# 5.net
KiCad netlist of a schematic drawn in EAGLE
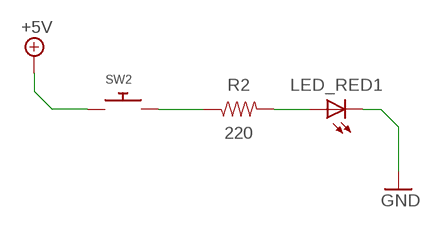
[diagram p0: schematic, sheet 1]
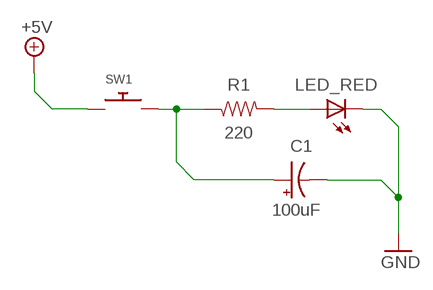
[diagram p1: schematic, sheet 2]

(export (version "E")
  (design (tool "Eeschema 10.0.6"))
  (components
    (comp (ref "LED_RED1")
      (value "LED5MM")
      (footprint "eagle-import:LED5MM")
      (libsource (lib "eagle-import") (part "LED5MM"))
    )
    (comp (ref "R2")
      (value "220")
      (footprint "eagle-import:AXIAL-0.3")
      (libsource (lib "eagle-import") (part "100OHM-HORIZ-1/4W-1%"))
    )
    (comp (ref "SW2")
      (value "SWITCH_PUSHBUTTONSOFTTOUCHSMD_SJ")
      (footprint "eagle-import:PUSHBUTTON_SMD_SJ")
      (libsource (lib "eagle-import") (part "SWITCH_PUSHBUTTONSOFTTOUCHSMD_SJ"))
    )
    (comp (ref "C1")
      (value "100uF")
      (footprint "eagle-import:CPOL-RADIAL-2.5MM-6.5MM")
      (libsource (lib "eagle-import") (part "100UF-POLAR-RADIAL-2.5MM-25V-20%"))
    )
    (comp (ref "LED_RED")
      (value "LED5MM")
      (footprint "eagle-import:LED5MM")
      (libsource (lib "eagle-import") (part "LED5MM"))
    )
    (comp (ref "R1")
      (value "220")
      (footprint "eagle-import:AXIAL-0.3")
      (libsource (lib "eagle-import") (part "100OHM-HORIZ-1/4W-1%"))
    )
    (comp (ref "SW1")
      (value "SWITCH_PUSHBUTTONSOFTTOUCHSMD_SJ")
      (footprint "eagle-import:PUSHBUTTON_SMD_SJ")
      (libsource (lib "eagle-import") (part "SWITCH_PUSHBUTTONSOFTTOUCHSMD_SJ"))
    )
  )
  (nets
    (net (code "1") (name "+5V") (class "Default")
      (node (ref "SW1") (pin "P$1") (pinfunction "P$1_P$1") (pintype "passive"))
      (node (ref "SW2") (pin "P$1") (pinfunction "P$1_P$1") (pintype "passive"))
    )
    (net (code "2") (name "GND") (class "Default")
      (node (ref "C1") (pin "2") (pinfunction "-_2") (pintype "passive"))
      (node (ref "LED_RED") (pin "K") (pinfunction "C_K") (pintype "passive"))
      (node (ref "LED_RED1") (pin "K") (pinfunction "C_K") (pintype "passive"))
    )
    (net (code "3") (name "Net-(C1-+)") (class "Default")
      (node (ref "C1") (pin "1") (pinfunction "+_1") (pintype "passive"))
      (node (ref "R1") (pin "P$1") (pinfunction "1_P$1") (pintype "passive"))
      (node (ref "SW1") (pin "P$2") (pinfunction "P$2_P$2") (pintype "passive"))
    )
    (net (code "4") (name "Net-(R1-2)") (class "Default")
      (node (ref "LED_RED") (pin "A") (pinfunction "A_A") (pintype "passive"))
      (node (ref "R1") (pin "P$2") (pinfunction "2_P$2") (pintype "passive"))
    )
    (net (code "5") (name "Net-(R2-1)") (class "Default")
      (node (ref "R2") (pin "P$1") (pinfunction "1_P$1") (pintype "passive"))
      (node (ref "SW2") (pin "P$2") (pinfunction "P$2_P$2") (pintype "passive"))
    )
    (net (code "6") (name "Net-(R2-2)") (class "Default")
      (node (ref "LED_RED1") (pin "A") (pinfunction "A_A") (pintype "passive"))
      (node (ref "R2") (pin "P$2") (pinfunction "2_P$2") (pintype "passive"))
    )
  )
)
